# Sheet1.net
KiCad netlist of a schematic drawn in Altium Designer
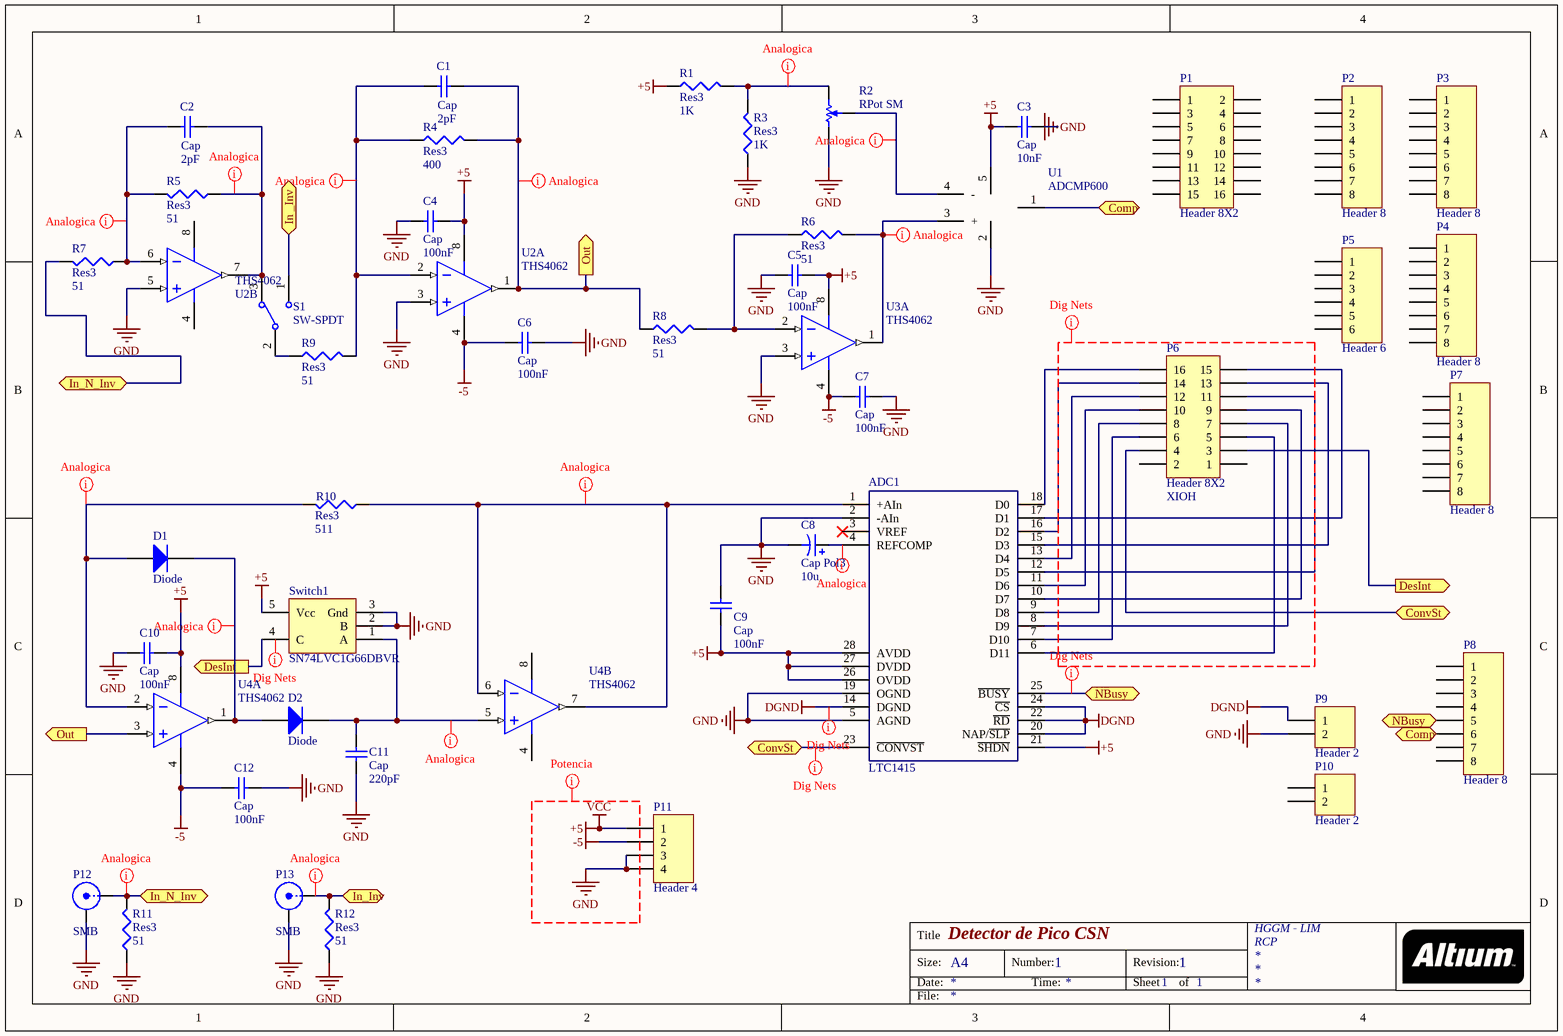
[diagram p0: Sheet1.SchDoc]

(export (version "E")
  (design (tool "Eeschema 10.0.6"))
  (components
    (comp (ref "ADC1")
      (value "LTC1415")
      (footprint "SO28_N")
      (libsource (lib "Integrated_Library1") (part "LTC1415"))
    )
    (comp (ref "C1")
      (value "Cap")
      (footprint "6-0805_N")
      (description "Capacitor")
      (fields (field (name "ALTIUM_VALUE") "2pF") (field (name "PUBLISHER") "Altium Limited"))
      (libsource (lib "Miscellaneous Devices") (part "Cap"))
    )
    (comp (ref "C2")
      (value "Cap")
      (footprint "6-0805_N")
      (description "Capacitor")
      (fields (field (name "ALTIUM_VALUE") "2pF") (field (name "PUBLISHER") "Altium Limited"))
      (libsource (lib "Miscellaneous Devices") (part "Cap"))
    )
    (comp (ref "C3")
      (value "Cap")
      (footprint "6-0805_N")
      (description "Capacitor")
      (fields (field (name "ALTIUM_VALUE") "10nF") (field (name "PUBLISHER") "Altium Limited"))
      (libsource (lib "Miscellaneous Devices") (part "Cap"))
    )
    (comp (ref "C4")
      (value "Cap")
      (footprint "6-0805_N")
      (description "Capacitor")
      (fields (field (name "ALTIUM_VALUE") "100nF") (field (name "PUBLISHER") "Altium Limited"))
      (libsource (lib "Miscellaneous Devices") (part "Cap"))
    )
    (comp (ref "C5")
      (value "Cap")
      (footprint "6-0805_N")
      (description "Capacitor")
      (fields (field (name "ALTIUM_VALUE") "100nF") (field (name "PUBLISHER") "Altium Limited"))
      (libsource (lib "Miscellaneous Devices") (part "Cap"))
    )
    (comp (ref "C6")
      (value "Cap")
      (footprint "6-0805_N")
      (description "Capacitor")
      (fields (field (name "ALTIUM_VALUE") "100nF") (field (name "PUBLISHER") "Altium Limited"))
      (libsource (lib "Miscellaneous Devices") (part "Cap"))
    )
    (comp (ref "C7")
      (value "Cap")
      (footprint "6-0805_N")
      (description "Capacitor")
      (fields (field (name "ALTIUM_VALUE") "100nF") (field (name "PUBLISHER") "Altium Limited"))
      (libsource (lib "Miscellaneous Devices") (part "Cap"))
    )
    (comp (ref "C8")
      (value "Cap Pol3")
      (footprint "C0805")
      (description "Polarized Capacitor (Surface Mount)")
      (fields (field (name "ALTIUM_VALUE") "10u") (field (name "PUBLISHER") "Altium Limited"))
      (libsource (lib "Miscellaneous Devices") (part "Cap Pol3"))
    )
    (comp (ref "C9")
      (value "Cap")
      (footprint "6-0805_N")
      (description "Capacitor")
      (fields (field (name "ALTIUM_VALUE") "100nF") (field (name "PUBLISHER") "Altium Limited"))
      (libsource (lib "Miscellaneous Devices") (part "Cap"))
    )
    (comp (ref "C10")
      (value "Cap")
      (footprint "6-0805_N")
      (description "Capacitor")
      (fields (field (name "ALTIUM_VALUE") "100nF") (field (name "PUBLISHER") "Altium Limited"))
      (libsource (lib "Miscellaneous Devices") (part "Cap"))
    )
    (comp (ref "C11")
      (value "Cap")
      (footprint "6-0805_N")
      (description "Capacitor")
      (fields (field (name "ALTIUM_VALUE") "220pF") (field (name "PUBLISHER") "Altium Limited"))
      (libsource (lib "Miscellaneous Devices") (part "Cap"))
    )
    (comp (ref "C12")
      (value "Cap")
      (footprint "6-0805_N")
      (description "Capacitor")
      (fields (field (name "ALTIUM_VALUE") "100nF") (field (name "PUBLISHER") "Altium Limited"))
      (libsource (lib "Miscellaneous Devices") (part "Cap"))
    )
    (comp (ref "D1")
      (value "Diode")
      (footprint "6-0805_N")
      (description "Default Diode")
      (fields (field (name "PUBLISHER") "Altium Limited"))
      (libsource (lib "Miscellaneous Devices") (part "Diode"))
    )
    (comp (ref "D2")
      (value "Diode")
      (footprint "6-0805_N")
      (description "Default Diode")
      (fields (field (name "PUBLISHER") "Altium Limited"))
      (libsource (lib "Miscellaneous Devices") (part "Diode"))
    )
    (comp (ref "P1")
      (value "Header 8X2")
      (footprint "HDR2X8")
      (description "Header, 8-Pin, Dual row")
      (fields (field (name "PUBLISHER") "Altium Limited"))
      (libsource (lib "") (part "Header 8X2_1"))
    )
    (comp (ref "P2")
      (value "Header 8")
      (footprint "HDR1X8")
      (description "Header, 8-Pin")
      (fields (field (name "PUBLISHER") "Altium Limited"))
      (libsource (lib "Miscellaneous Connectors") (part "Header 8"))
    )
    (comp (ref "P3")
      (value "Header 8")
      (footprint "HDR1X8")
      (description "Header, 8-Pin")
      (fields (field (name "PUBLISHER") "Altium Limited"))
      (libsource (lib "Miscellaneous Connectors") (part "Header 8"))
    )
    (comp (ref "P4")
      (value "Header 8")
      (footprint "HDR1X8")
      (description "Header, 8-Pin")
      (fields (field (name "PUBLISHER") "Altium Limited"))
      (libsource (lib "Miscellaneous Connectors") (part "Header 8"))
    )
    (comp (ref "P5")
      (value "Header 6")
      (footprint "HDR1X6")
      (description "Header, 6-Pin")
      (fields (field (name "PUBLISHER") "Altium Limited"))
      (libsource (lib "Miscellaneous Connectors") (part "Header 6"))
    )
    (comp (ref "P6")
      (value "Header 8X2")
      (footprint "HDR2X8")
      (description "Header, 8-Pin, Dual row")
      (fields (field (name "CON_ARDUINO") "XIOH") (field (name "PUBLISHER") "Altium Limited"))
      (libsource (lib "Miscellaneous Connectors") (part "Header 8X2"))
    )
    (comp (ref "P7")
      (value "Header 8")
      (footprint "HDR1X8")
      (description "Header, 8-Pin")
      (fields (field (name "PUBLISHER") "Altium Limited"))
      (libsource (lib "Miscellaneous Connectors") (part "Header 8"))
    )
    (comp (ref "P8")
      (value "Header 8")
      (footprint "HDR1X8")
      (description "Header, 8-Pin")
      (fields (field (name "PUBLISHER") "Altium Limited"))
      (libsource (lib "Miscellaneous Connectors") (part "Header 8"))
    )
    (comp (ref "P9")
      (value "Header 2")
      (footprint "HDR1X2")
      (description "Header, 2-Pin")
      (fields (field (name "PUBLISHER") "Altium Limited"))
      (libsource (lib "Miscellaneous Connectors") (part "Header 2"))
    )
    (comp (ref "P10")
      (value "Header 2")
      (footprint "HDR1X2")
      (description "Header, 2-Pin")
      (fields (field (name "PUBLISHER") "Altium Limited"))
      (libsource (lib "Miscellaneous Connectors") (part "Header 2"))
    )
    (comp (ref "P11")
      (value "Header 4")
      (footprint "HDR1X4")
      (description "Header, 4-Pin")
      (fields (field (name "PUBLISHER") "Altium Limited"))
      (libsource (lib "Miscellaneous Connectors") (part "Header 4"))
    )
    (comp (ref "P12")
      (value "SMB")
      (footprint "SMB_V-RJ45")
      (description "SMB Straight Connector")
      (fields (field (name "PUBLISHER") "Altium Limited"))
      (libsource (lib "Miscellaneous Connectors") (part "SMB"))
    )
    (comp (ref "P13")
      (value "SMB")
      (footprint "SMB_V-RJ45")
      (description "SMB Straight Connector")
      (fields (field (name "PUBLISHER") "Altium Limited"))
      (libsource (lib "Miscellaneous Connectors") (part "SMB"))
    )
    (comp (ref "R1")
      (value "Res3")
      (footprint "6-0805_N")
      (description "Resistor")
      (fields (field (name "ALTIUM_VALUE") "1K") (field (name "PUBLISHER") "Altium Limited"))
      (libsource (lib "Miscellaneous Devices") (part "Res3"))
    )
    (comp (ref "R2")
      (value "RPot SM")
      (footprint "POT4MM-2")
      (description "Square Trimming Potentiometer")
      (fields (field (name "PUBLISHER") "Altium Limited"))
      (libsource (lib "Miscellaneous Devices") (part "RPot SM"))
    )
    (comp (ref "R3")
      (value "Res3")
      (footprint "6-0805_N")
      (description "Resistor")
      (fields (field (name "ALTIUM_VALUE") "1K") (field (name "PUBLISHER") "Altium Limited"))
      (libsource (lib "Miscellaneous Devices") (part "Res3"))
    )
    (comp (ref "R4")
      (value "Res3")
      (footprint "6-0805_N")
      (description "Resistor")
      (fields (field (name "ALTIUM_VALUE") "400") (field (name "PUBLISHER") "Altium Limited"))
      (libsource (lib "Miscellaneous Devices") (part "Res3"))
    )
    (comp (ref "R5")
      (value "Res3")
      (footprint "6-0805_N")
      (description "Resistor")
      (fields (field (name "ALTIUM_VALUE") "51") (field (name "PUBLISHER") "Altium Limited"))
      (libsource (lib "Miscellaneous Devices") (part "Res3"))
    )
    (comp (ref "R6")
      (value "Res3")
      (footprint "6-0805_N")
      (description "Resistor")
      (fields (field (name "ALTIUM_VALUE") "51") (field (name "PUBLISHER") "Altium Limited"))
      (libsource (lib "Miscellaneous Devices") (part "Res3"))
    )
    (comp (ref "R7")
      (value "Res3")
      (footprint "6-0805_N")
      (description "Resistor")
      (fields (field (name "ALTIUM_VALUE") "51") (field (name "PUBLISHER") "Altium Limited"))
      (libsource (lib "Miscellaneous Devices") (part "Res3"))
    )
    (comp (ref "R8")
      (value "Res3")
      (footprint "6-0805_N")
      (description "Resistor")
      (fields (field (name "ALTIUM_VALUE") "51") (field (name "PUBLISHER") "Altium Limited"))
      (libsource (lib "Miscellaneous Devices") (part "Res3"))
    )
    (comp (ref "R9")
      (value "Res3")
      (footprint "6-0805_N")
      (description "Resistor")
      (fields (field (name "ALTIUM_VALUE") "51") (field (name "PUBLISHER") "Altium Limited"))
      (libsource (lib "Miscellaneous Devices") (part "Res3"))
    )
    (comp (ref "R10")
      (value "Res3")
      (footprint "6-0805_N")
      (description "Resistor")
      (fields (field (name "ALTIUM_VALUE") "511") (field (name "PUBLISHER") "Altium Limited"))
      (libsource (lib "Miscellaneous Devices") (part "Res3"))
    )
    (comp (ref "R11")
      (value "Res3")
      (footprint "6-0805_N")
      (description "Resistor")
      (fields (field (name "ALTIUM_VALUE") "51") (field (name "PUBLISHER") "Altium Limited"))
      (libsource (lib "Miscellaneous Devices") (part "Res3"))
    )
    (comp (ref "R12")
      (value "Res3")
      (footprint "6-0805_N")
      (description "Resistor")
      (fields (field (name "ALTIUM_VALUE") "51") (field (name "PUBLISHER") "Altium Limited"))
      (libsource (lib "Miscellaneous Devices") (part "Res3"))
    )
    (comp (ref "S1")
      (value "SW-SPDT")
      (footprint "HDR1X3")
      (description "SPDT Subminiature Toggle Switch, Right Angle Mounting, Vertical Actuation")
      (fields (field (name "PUBLISHER") "Altium Limited"))
      (libsource (lib "Miscellaneous Devices") (part "SW-SPDT"))
    )
    (comp (ref "Switch1")
      (value "SN74LVC1G66DBVR")
      (footprint "SOT23-5_N")
      (libsource (lib "Integrated_Library1") (part "SN74LVC1G66DBVR"))
    )
    (comp (ref "U1") (value "ADCMP600") (footprint "SOT23-5_N") (libsource (lib "Schlib1") (part "ADCMP600")))
    (comp (ref "U2")
      (value "THS4062")
      (footprint "S8_N")
      (description "Low Cost Dual Video Amplifier")
      (fields (field (name "PUBLISHER") "Altium Limited"))
      (libsource (lib "LT Video Amplifier") (part "LT1253CS8"))
    )
    (comp (ref "U3")
      (value "THS4062")
      (footprint "S8_N")
      (description "Low Cost Dual Video Amplifier")
      (fields (field (name "PUBLISHER") "Altium Limited"))
      (libsource (lib "LT Video Amplifier") (part "LT1253CS8"))
    )
    (comp (ref "U4")
      (value "THS4062")
      (footprint "S8_N")
      (description "Low Cost Dual Video Amplifier")
      (fields (field (name "PUBLISHER") "Altium Limited"))
      (libsource (lib "LT Video Amplifier") (part "LT1253CS8"))
    )
  )
  (nets
    (net (code "1") (name "+5") (class "Default")
      (node (ref "ADC1") (pin "21") (pinfunction "~{SHDN}_21") (pintype "passive"))
      (node (ref "ADC1") (pin "26") (pinfunction "OVDD_26") (pintype "passive"))
      (node (ref "ADC1") (pin "27") (pinfunction "DVDD_27") (pintype "passive"))
      (node (ref "ADC1") (pin "28") (pinfunction "AVDD_28") (pintype "passive"))
      (node (ref "C10") (pin "2") (pinfunction "2_2") (pintype "passive"))
      (node (ref "C3") (pin "1") (pinfunction "1_1") (pintype "passive"))
      (node (ref "C4") (pin "2") (pinfunction "2_2") (pintype "passive"))
      (node (ref "C5") (pin "2") (pinfunction "2_2") (pintype "passive"))
      (node (ref "C9") (pin "1") (pinfunction "1_1") (pintype "passive"))
      (node (ref "P11") (pin "1") (pinfunction "1_1") (pintype "passive"))
      (node (ref "R1") (pin "1") (pinfunction "1_1") (pintype "passive"))
      (node (ref "Switch1") (pin "5") (pinfunction "Vcc_5") (pintype "passive"))
      (node (ref "U1") (pin "5") (pintype "power_in"))
      (node (ref "U2") (pin "8") (pinfunction "V+_8") (pintype "power_in"))
      (node (ref "U3") (pin "8") (pinfunction "V+_8") (pintype "power_in"))
      (node (ref "U4") (pin "8") (pinfunction "V+_8") (pintype "power_in"))
    )
    (net (code "2") (name "-5") (class "Default")
      (node (ref "C12") (pin "1") (pinfunction "1_1") (pintype "passive"))
      (node (ref "C6") (pin "1") (pinfunction "1_1") (pintype "passive"))
      (node (ref "C7") (pin "1") (pinfunction "1_1") (pintype "passive"))
      (node (ref "P11") (pin "2") (pinfunction "2_2") (pintype "passive"))
      (node (ref "U2") (pin "4") (pinfunction "V-_4") (pintype "power_in"))
      (node (ref "U3") (pin "4") (pinfunction "V-_4") (pintype "power_in"))
      (node (ref "U4") (pin "4") (pinfunction "V-_4") (pintype "power_in"))
    )
    (net (code "3") (name "/Comp") (class "Default")
      (node (ref "P8") (pin "6") (pinfunction "6_6") (pintype "passive"))
      (node (ref "U1") (pin "1") (pintype "passive"))
    )
    (net (code "4") (name "/ConvSt") (class "Default")
      (node (ref "ADC1") (pin "23") (pinfunction "~{CONVST}_23") (pintype "passive"))
      (node (ref "P6") (pin "4") (pinfunction "4_4") (pintype "passive"))
    )
    (net (code "5") (name "/DesInt") (class "Default")
      (node (ref "P6") (pin "3") (pinfunction "3_3") (pintype "passive"))
      (node (ref "Switch1") (pin "4") (pinfunction "C_4") (pintype "passive"))
    )
    (net (code "6") (name "/In _Inv") (class "Default")
      (node (ref "S1") (pin "1") (pinfunction "1_1") (pintype "passive"))
    )
    (net (code "7") (name "/In_Inv") (class "Default")
      (node (ref "P13") (pin "1") (pinfunction "X_1") (pintype "passive"))
      (node (ref "R12") (pin "2") (pinfunction "2_2") (pintype "passive"))
    )
    (net (code "8") (name "/In_N_Inv") (class "Default")
      (node (ref "P12") (pin "1") (pinfunction "X_1") (pintype "passive"))
      (node (ref "R11") (pin "2") (pinfunction "2_2") (pintype "passive"))
      (node (ref "R7") (pin "2") (pinfunction "2_2") (pintype "passive"))
    )
    (net (code "9") (name "/NBusy") (class "Default")
      (node (ref "ADC1") (pin "25") (pinfunction "~{BUSY}_25") (pintype "passive"))
      (node (ref "P8") (pin "5") (pinfunction "5_5") (pintype "passive"))
    )
    (net (code "10") (name "/Out") (class "Default")
      (node (ref "C1") (pin "2") (pinfunction "2_2") (pintype "passive"))
      (node (ref "R4") (pin "2") (pinfunction "2_2") (pintype "passive"))
      (node (ref "R8") (pin "1") (pinfunction "1_1") (pintype "passive"))
      (node (ref "U2") (pin "1") (pinfunction "OUT_1") (pintype "output"))
      (node (ref "U4") (pin "3") (pinfunction "IN+_3") (pintype "input"))
    )
    (net (code "11") (name "DGND") (class "Default")
      (node (ref "ADC1") (pin "14") (pinfunction "DGND_14") (pintype "passive"))
      (node (ref "ADC1") (pin "20") (pinfunction "NAP/~{SLP}_20") (pintype "passive"))
      (node (ref "ADC1") (pin "22") (pinfunction "~{RD}_22") (pintype "passive"))
      (node (ref "ADC1") (pin "24") (pinfunction "~{CS}_24") (pintype "passive"))
      (node (ref "P9") (pin "1") (pinfunction "1_1") (pintype "passive"))
    )
    (net (code "12") (name "GND") (class "Default")
      (node (ref "ADC1") (pin "19") (pinfunction "OGND_19") (pintype "passive"))
      (node (ref "ADC1") (pin "2") (pinfunction "-AIn_2") (pintype "passive"))
      (node (ref "ADC1") (pin "5") (pinfunction "AGND_5") (pintype "passive"))
      (node (ref "C10") (pin "1") (pinfunction "1_1") (pintype "passive"))
      (node (ref "C11") (pin "1") (pinfunction "1_1") (pintype "passive"))
      (node (ref "C12") (pin "2") (pinfunction "2_2") (pintype "passive"))
      (node (ref "C4") (pin "1") (pinfunction "1_1") (pintype "passive"))
      (node (ref "C5") (pin "1") (pinfunction "1_1") (pintype "passive"))
      (node (ref "C6") (pin "2") (pinfunction "2_2") (pintype "passive"))
      (node (ref "C7") (pin "2") (pinfunction "2_2") (pintype "passive"))
      (node (ref "C8") (pin "2") (pinfunction "2_2") (pintype "passive"))
      (node (ref "C9") (pin "2") (pinfunction "2_2") (pintype "passive"))
      (node (ref "P11") (pin "3") (pinfunction "3_3") (pintype "passive"))
      (node (ref "P11") (pin "4") (pinfunction "4_4") (pintype "passive"))
      (node (ref "P12") (pin "2") (pinfunction "Y_2") (pintype "passive"))
      (node (ref "P13") (pin "2") (pinfunction "Y_2") (pintype "passive"))
      (node (ref "P9") (pin "2") (pinfunction "2_2") (pintype "passive"))
      (node (ref "R11") (pin "1") (pinfunction "1_1") (pintype "passive"))
      (node (ref "R12") (pin "1") (pinfunction "1_1") (pintype "passive"))
      (node (ref "R2") (pin "CCW") (pinfunction "-_CCW") (pintype "passive"))
      (node (ref "R3") (pin "1") (pinfunction "1_1") (pintype "passive"))
      (node (ref "Switch1") (pin "2") (pinfunction "B_2") (pintype "passive"))
      (node (ref "Switch1") (pin "3") (pinfunction "Gnd_3") (pintype "passive"))
      (node (ref "U1") (pin "2") (pintype "power_in"))
      (node (ref "U2") (pin "3") (pinfunction "IN+_3") (pintype "input"))
      (node (ref "U2") (pin "5") (pinfunction "IN+_5") (pintype "input"))
      (node (ref "U3") (pin "3") (pinfunction "IN+_3") (pintype "input"))
    )
    (net (code "13") (name "Net-(ADC1-+AIn)") (class "Default")
      (node (ref "ADC1") (pin "1") (pinfunction "+AIn_1") (pintype "passive"))
      (node (ref "R10") (pin "1") (pinfunction "1_1") (pintype "passive"))
      (node (ref "U4") (pin "6") (pinfunction "IN-_6") (pintype "input"))
      (node (ref "U4") (pin "7") (pinfunction "OUT_7") (pintype "output"))
    )
    (net (code "14") (name "Net-(ADC1-D0)") (class "Default")
      (node (ref "ADC1") (pin "18") (pinfunction "D0_18") (pintype "passive"))
      (node (ref "P6") (pin "16") (pinfunction "16_16") (pintype "passive"))
    )
    (net (code "15") (name "Net-(ADC1-D1)") (class "Default")
      (node (ref "ADC1") (pin "17") (pinfunction "D1_17") (pintype "passive"))
      (node (ref "P6") (pin "15") (pinfunction "15_15") (pintype "passive"))
    )
    (net (code "16") (name "Net-(ADC1-D2)") (class "Default")
      (node (ref "ADC1") (pin "16") (pinfunction "D2_16") (pintype "passive"))
      (node (ref "P6") (pin "14") (pinfunction "14_14") (pintype "passive"))
    )
    (net (code "17") (name "Net-(ADC1-D3)") (class "Default")
      (node (ref "ADC1") (pin "15") (pinfunction "D3_15") (pintype "passive"))
      (node (ref "P6") (pin "13") (pinfunction "13_13") (pintype "passive"))
    )
    (net (code "18") (name "Net-(ADC1-D4)") (class "Default")
      (node (ref "ADC1") (pin "13") (pinfunction "D4_13") (pintype "passive"))
      (node (ref "P6") (pin "12") (pinfunction "12_12") (pintype "passive"))
    )
    (net (code "19") (name "Net-(ADC1-D5)") (class "Default")
      (node (ref "ADC1") (pin "12") (pinfunction "D5_12") (pintype "passive"))
      (node (ref "P6") (pin "11") (pinfunction "11_11") (pintype "passive"))
    )
    (net (code "20") (name "Net-(ADC1-D6)") (class "Default")
      (node (ref "ADC1") (pin "11") (pinfunction "D6_11") (pintype "passive"))
      (node (ref "P6") (pin "10") (pinfunction "10_10") (pintype "passive"))
    )
    (net (code "21") (name "Net-(ADC1-D7)") (class "Default")
      (node (ref "ADC1") (pin "10") (pinfunction "D7_10") (pintype "passive"))
      (node (ref "P6") (pin "9") (pinfunction "9_9") (pintype "passive"))
    )
    (net (code "22") (name "Net-(ADC1-D8)") (class "Default")
      (node (ref "ADC1") (pin "9") (pinfunction "D8_9") (pintype "passive"))
      (node (ref "P6") (pin "8") (pinfunction "8_8") (pintype "passive"))
    )
    (net (code "23") (name "Net-(ADC1-D9)") (class "Default")
      (node (ref "ADC1") (pin "8") (pinfunction "D9_8") (pintype "passive"))
      (node (ref "P6") (pin "7") (pinfunction "7_7") (pintype "passive"))
    )
    (net (code "24") (name "Net-(ADC1-D10)") (class "Default")
      (node (ref "ADC1") (pin "7") (pinfunction "D10_7") (pintype "passive"))
      (node (ref "P6") (pin "6") (pinfunction "6_6") (pintype "passive"))
    )
    (net (code "25") (name "Net-(ADC1-D11)") (class "Default")
      (node (ref "ADC1") (pin "6") (pinfunction "D11_6") (pintype "passive"))
      (node (ref "P6") (pin "5") (pinfunction "5_5") (pintype "passive"))
    )
    (net (code "26") (name "Net-(ADC1-REFCOMP)") (class "Default")
      (node (ref "ADC1") (pin "4") (pinfunction "REFCOMP_4") (pintype "passive"))
      (node (ref "C8") (pin "1") (pinfunction "1_1") (pintype "passive"))
    )
    (net (code "27") (name "Net-(D1-A)") (class "Default")
      (node (ref "D1") (pin "1") (pinfunction "A_1") (pintype "passive"))
      (node (ref "R10") (pin "2") (pinfunction "2_2") (pintype "passive"))
      (node (ref "U4") (pin "2") (pinfunction "IN-_2") (pintype "input"))
    )
    (net (code "28") (name "Net-(D1-K)") (class "Default")
      (node (ref "D1") (pin "2") (pinfunction "K_2") (pintype "passive"))
      (node (ref "D2") (pin "1") (pinfunction "A_1") (pintype "passive"))
      (node (ref "U4") (pin "1") (pinfunction "OUT_1") (pintype "output"))
    )
    (net (code "29") (name "Net-(D2-K)") (class "Default")
      (node (ref "C11") (pin "2") (pinfunction "2_2") (pintype "passive"))
      (node (ref "D2") (pin "2") (pinfunction "K_2") (pintype "passive"))
      (node (ref "Switch1") (pin "1") (pinfunction "A_1") (pintype "passive"))
      (node (ref "U4") (pin "5") (pinfunction "IN+_5") (pintype "input"))
    )
    (net (code "30") (name "Net-(R2-+)") (class "Default")
      (node (ref "R1") (pin "2") (pinfunction "2_2") (pintype "passive"))
      (node (ref "R2") (pin "CW") (pinfunction "+_CW") (pintype "passive"))
      (node (ref "R3") (pin "2") (pinfunction "2_2") (pintype "passive"))
    )
    (net (code "31") (name "Net-(R9-Pad1)") (class "Default")
      (node (ref "R9") (pin "1") (pinfunction "1_1") (pintype "passive"))
      (node (ref "S1") (pin "2") (pinfunction "2_2") (pintype "passive"))
    )
    (net (code "32") (name "Net-(U1-+)") (class "Default")
      (node (ref "R6") (pin "2") (pinfunction "2_2") (pintype "passive"))
      (node (ref "U1") (pin "3") (pinfunction "+_3") (pintype "passive"))
      (node (ref "U3") (pin "1") (pinfunction "OUT_1") (pintype "output"))
    )
    (net (code "33") (name "Net-(U1--)") (class "Default")
      (node (ref "R2") (pin "W") (pinfunction "W_W") (pintype "passive"))
      (node (ref "U1") (pin "4") (pinfunction "-_4") (pintype "passive"))
    )
    (net (code "34") (name "Net-(U2A-IN-)") (class "Default")
      (node (ref "C1") (pin "1") (pinfunction "1_1") (pintype "passive"))
      (node (ref "R4") (pin "1") (pinfunction "1_1") (pintype "passive"))
      (node (ref "R9") (pin "2") (pinfunction "2_2") (pintype "passive"))
      (node (ref "U2") (pin "2") (pinfunction "IN-_2") (pintype "input"))
    )
    (net (code "35") (name "Net-(U2B-IN-)") (class "Default")
      (node (ref "C2") (pin "1") (pinfunction "1_1") (pintype "passive"))
      (node (ref "R5") (pin "2") (pinfunction "2_2") (pintype "passive"))
      (node (ref "R7") (pin "1") (pinfunction "1_1") (pintype "passive"))
      (node (ref "U2") (pin "6") (pinfunction "IN-_6") (pintype "input"))
    )
    (net (code "36") (name "Net-(U2B-OUT)") (class "Default")
      (node (ref "C2") (pin "2") (pinfunction "2_2") (pintype "passive"))
      (node (ref "R5") (pin "1") (pinfunction "1_1") (pintype "passive"))
      (node (ref "S1") (pin "3") (pinfunction "3_3") (pintype "passive"))
      (node (ref "U2") (pin "7") (pinfunction "OUT_7") (pintype "output"))
    )
    (net (code "37") (name "Net-(U3A-IN-)") (class "Default")
      (node (ref "R6") (pin "1") (pinfunction "1_1") (pintype "passive"))
      (node (ref "R8") (pin "2") (pinfunction "2_2") (pintype "passive"))
      (node (ref "U3") (pin "2") (pinfunction "IN-_2") (pintype "input"))
    )
    (net (code "38") (name "unconnected-(ADC1-VREF-Pad3)") (class "Default")
      (node (ref "ADC1") (pin "3") (pinfunction "VREF_3") (pintype "passive+no_connect"))
    )
    (net (code "39") (name "unconnected-(C3-Pad2)") (class "Default")
      (node (ref "C3") (pin "2") (pinfunction "2_2") (pintype "passive"))
    )
    (net (code "40") (name "unconnected-(P1-Pad1)") (class "Default")
      (node (ref "P1") (pin "1") (pinfunction "1_1") (pintype "passive"))
    )
    (net (code "41") (name "unconnected-(P1-Pad2)") (class "Default")
      (node (ref "P1") (pin "2") (pinfunction "2_2") (pintype "passive"))
    )
    (net (code "42") (name "unconnected-(P1-Pad3)") (class "Default")
      (node (ref "P1") (pin "3") (pinfunction "3_3") (pintype "passive"))
    )
    (net (code "43") (name "unconnected-(P1-Pad4)") (class "Default")
      (node (ref "P1") (pin "4") (pinfunction "4_4") (pintype "passive"))
    )
    (net (code "44") (name "unconnected-(P1-Pad5)") (class "Default")
      (node (ref "P1") (pin "5") (pinfunction "5_5") (pintype "passive"))
    )
    (net (code "45") (name "unconnected-(P1-Pad6)") (class "Default")
      (node (ref "P1") (pin "6") (pinfunction "6_6") (pintype "passive"))
    )
    (net (code "46") (name "unconnected-(P1-Pad7)") (class "Default")
      (node (ref "P1") (pin "7") (pinfunction "7_7") (pintype "passive"))
    )
    (net (code "47") (name "unconnected-(P1-Pad8)") (class "Default")
      (node (ref "P1") (pin "8") (pinfunction "8_8") (pintype "passive"))
    )
    (net (code "48") (name "unconnected-(P1-Pad9)") (class "Default")
      (node (ref "P1") (pin "9") (pinfunction "9_9") (pintype "passive"))
    )
    (net (code "49") (name "unconnected-(P1-Pad10)") (class "Default")
      (node (ref "P1") (pin "10") (pinfunction "10_10") (pintype "passive"))
    )
    (net (code "50") (name "unconnected-(P1-Pad11)") (class "Default")
      (node (ref "P1") (pin "11") (pinfunction "11_11") (pintype "passive"))
    )
    (net (code "51") (name "unconnected-(P1-Pad12)") (class "Default")
      (node (ref "P1") (pin "12") (pinfunction "12_12") (pintype "passive"))
    )
    (net (code "52") (name "unconnected-(P1-Pad13)") (class "Default")
      (node (ref "P1") (pin "13") (pinfunction "13_13") (pintype "passive"))
    )
    (net (code "53") (name "unconnected-(P1-Pad14)") (class "Default")
      (node (ref "P1") (pin "14") (pinfunction "14_14") (pintype "passive"))
    )
    (net (code "54") (name "unconnected-(P1-Pad15)") (class "Default")
      (node (ref "P1") (pin "15") (pinfunction "15_15") (pintype "passive"))
    )
    (net (code "55") (name "unconnected-(P1-Pad16)") (class "Default")
      (node (ref "P1") (pin "16") (pinfunction "16_16") (pintype "passive"))
    )
    (net (code "56") (name "unconnected-(P2-Pad1)") (class "Default")
      (node (ref "P2") (pin "1") (pinfunction "1_1") (pintype "passive"))
    )
    (net (code "57") (name "unconnected-(P2-Pad2)") (class "Default")
      (node (ref "P2") (pin "2") (pinfunction "2_2") (pintype "passive"))
    )
    (net (code "58") (name "unconnected-(P2-Pad3)") (class "Default")
      (node (ref "P2") (pin "3") (pinfunction "3_3") (pintype "passive"))
    )
    (net (code "59") (name "unconnected-(P2-Pad4)") (class "Default")
      (node (ref "P2") (pin "4") (pinfunction "4_4") (pintype "passive"))
    )
    (net (code "60") (name "unconnected-(P2-Pad5)") (class "Default")
      (node (ref "P2") (pin "5") (pinfunction "5_5") (pintype "passive"))
    )
    (net (code "61") (name "unconnected-(P2-Pad6)") (class "Default")
      (node (ref "P2") (pin "6") (pinfunction "6_6") (pintype "passive"))
    )
    (net (code "62") (name "unconnected-(P2-Pad7)") (class "Default")
      (node (ref "P2") (pin "7") (pinfunction "7_7") (pintype "passive"))
    )
    (net (code "63") (name "unconnected-(P2-Pad8)") (class "Default")
      (node (ref "P2") (pin "8") (pinfunction "8_8") (pintype "passive"))
    )
    (net (code "64") (name "unconnected-(P3-Pad1)") (class "Default")
      (node (ref "P3") (pin "1") (pinfunction "1_1") (pintype "passive"))
    )
    (net (code "65") (name "unconnected-(P3-Pad2)") (class "Default")
      (node (ref "P3") (pin "2") (pinfunction "2_2") (pintype "passive"))
    )
    (net (code "66") (name "unconnected-(P3-Pad3)") (class "Default")
      (node (ref "P3") (pin "3") (pinfunction "3_3") (pintype "passive"))
    )
    (net (code "67") (name "unconnected-(P3-Pad4)") (class "Default")
      (node (ref "P3") (pin "4") (pinfunction "4_4") (pintype "passive"))
    )
    (net (code "68") (name "unconnected-(P3-Pad5)") (class "Default")
      (node (ref "P3") (pin "5") (pinfunction "5_5") (pintype "passive"))
    )
    (net (code "69") (name "unconnected-(P3-Pad6)") (class "Default")
      (node (ref "P3") (pin "6") (pinfunction "6_6") (pintype "passive"))
    )
    (net (code "70") (name "unconnected-(P3-Pad7)") (class "Default")
      (node (ref "P3") (pin "7") (pinfunction "7_7") (pintype "passive"))
    )
    (net (code "71") (name "unconnected-(P3-Pad8)") (class "Default")
      (node (ref "P3") (pin "8") (pinfunction "8_8") (pintype "passive"))
    )
    (net (code "72") (name "unconnected-(P4-Pad1)") (class "Default")
      (node (ref "P4") (pin "1") (pinfunction "1_1") (pintype "passive"))
    )
    (net (code "73") (name "unconnected-(P4-Pad2)") (class "Default")
      (node (ref "P4") (pin "2") (pinfunction "2_2") (pintype "passive"))
    )
    (net (code "74") (name "unconnected-(P4-Pad3)") (class "Default")
      (node (ref "P4") (pin "3") (pinfunction "3_3") (pintype "passive"))
    )
    (net (code "75") (name "unconnected-(P4-Pad4)") (class "Default")
      (node (ref "P4") (pin "4") (pinfunction "4_4") (pintype "passive"))
    )
    (net (code "76") (name "unconnected-(P4-Pad5)") (class "Default")
      (node (ref "P4") (pin "5") (pinfunction "5_5") (pintype "passive"))
    )
    (net (code "77") (name "unconnected-(P4-Pad6)") (class "Default")
      (node (ref "P4") (pin "6") (pinfunction "6_6") (pintype "passive"))
    )
    (net (code "78") (name "unconnected-(P4-Pad7)") (class "Default")
      (node (ref "P4") (pin "7") (pinfunction "7_7") (pintype "passive"))
    )
    (net (code "79") (name "unconnected-(P4-Pad8)") (class "Default")
      (node (ref "P4") (pin "8") (pinfunction "8_8") (pintype "passive"))
    )
    (net (code "80") (name "unconnected-(P5-Pad1)") (class "Default")
      (node (ref "P5") (pin "1") (pinfunction "1_1") (pintype "passive"))
    )
    (net (code "81") (name "unconnected-(P5-Pad2)") (class "Default")
      (node (ref "P5") (pin "2") (pinfunction "2_2") (pintype "passive"))
    )
    (net (code "82") (name "unconnected-(P5-Pad3)") (class "Default")
      (node (ref "P5") (pin "3") (pinfunction "3_3") (pintype "passive"))
    )
    (net (code "83") (name "unconnected-(P5-Pad4)") (class "Default")
      (node (ref "P5") (pin "4") (pinfunction "4_4") (pintype "passive"))
    )
    (net (code "84") (name "unconnected-(P5-Pad5)") (class "Default")
      (node (ref "P5") (pin "5") (pinfunction "5_5") (pintype "passive"))
    )
    (net (code "85") (name "unconnected-(P5-Pad6)") (class "Default")
      (node (ref "P5") (pin "6") (pinfunction "6_6") (pintype "passive"))
    )
    (net (code "86") (name "unconnected-(P6-Pad1)") (class "Default")
      (node (ref "P6") (pin "1") (pinfunction "1_1") (pintype "passive"))
    )
    (net (code "87") (name "unconnected-(P6-Pad2)") (class "Default")
      (node (ref "P6") (pin "2") (pinfunction "2_2") (pintype "passive"))
    )
    (net (code "88") (name "unconnected-(P7-Pad1)") (class "Default")
      (node (ref "P7") (pin "1") (pinfunction "1_1") (pintype "passive"))
    )
    (net (code "89") (name "unconnected-(P7-Pad2)") (class "Default")
      (node (ref "P7") (pin "2") (pinfunction "2_2") (pintype "passive"))
    )
    (net (code "90") (name "unconnected-(P7-Pad3)") (class "Default")
      (node (ref "P7") (pin "3") (pinfunction "3_3") (pintype "passive"))
    )
    (net (code "91") (name "unconnected-(P7-Pad4)") (class "Default")
      (node (ref "P7") (pin "4") (pinfunction "4_4") (pintype "passive"))
    )
    (net (code "92") (name "unconnected-(P7-Pad5)") (class "Default")
      (node (ref "P7") (pin "5") (pinfunction "5_5") (pintype "passive"))
    )
    (net (code "93") (name "unconnected-(P7-Pad6)") (class "Default")
      (node (ref "P7") (pin "6") (pinfunction "6_6") (pintype "passive"))
    )
    (net (code "94") (name "unconnected-(P7-Pad7)") (class "Default")
      (node (ref "P7") (pin "7") (pinfunction "7_7") (pintype "passive"))
    )
    (net (code "95") (name "unconnected-(P7-Pad8)") (class "Default")
      (node (ref "P7") (pin "8") (pinfunction "8_8") (pintype "passive"))
    )
    (net (code "96") (name "unconnected-(P8-Pad1)") (class "Default")
      (node (ref "P8") (pin "1") (pinfunction "1_1") (pintype "passive"))
    )
    (net (code "97") (name "unconnected-(P8-Pad2)") (class "Default")
      (node (ref "P8") (pin "2") (pinfunction "2_2") (pintype "passive"))
    )
    (net (code "98") (name "unconnected-(P8-Pad3)") (class "Default")
      (node (ref "P8") (pin "3") (pinfunction "3_3") (pintype "passive"))
    )
    (net (code "99") (name "unconnected-(P8-Pad4)") (class "Default")
      (node (ref "P8") (pin "4") (pinfunction "4_4") (pintype "passive"))
    )
    (net (code "100") (name "unconnected-(P8-Pad7)") (class "Default")
      (node (ref "P8") (pin "7") (pinfunction "7_7") (pintype "passive"))
    )
    (net (code "101") (name "unconnected-(P8-Pad8)") (class "Default")
      (node (ref "P8") (pin "8") (pinfunction "8_8") (pintype "passive"))
    )
    (net (code "102") (name "unconnected-(P10-Pad1)") (class "Default")
      (node (ref "P10") (pin "1") (pinfunction "1_1") (pintype "passive"))
    )
    (net (code "103") (name "unconnected-(P10-Pad2)") (class "Default")
      (node (ref "P10") (pin "2") (pinfunction "2_2") (pintype "passive"))
    )
    (net (code "104") (name "unconnected-(U2B-V+-Pad8)") (class "Default")
      (node (ref "U2") (pin "8") (pinfunction "V+_8") (pintype "power_in"))
    )
    (net (code "105") (name "unconnected-(U2B-V--Pad4)") (class "Default")
      (node (ref "U2") (pin "4") (pinfunction "V-_4") (pintype "power_in"))
    )
    (net (code "106") (name "unconnected-(U4B-V+-Pad8)") (class "Default")
      (node (ref "U4") (pin "8") (pinfunction "V+_8") (pintype "power_in"))
    )
    (net (code "107") (name "unconnected-(U4B-V--Pad4)") (class "Default")
      (node (ref "U4") (pin "4") (pinfunction "V-_4") (pintype "power_in"))
    )
  )
)
